# oledboard.net
KiCad netlist of a schematic drawn in EAGLE
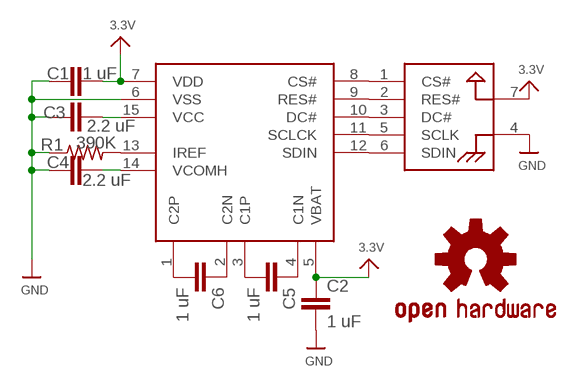
[diagram p0: schematic, sheet 1]

(export (version "E")
  (design (tool "Eeschema 10.0.6"))
  (components
    (comp (ref "C1")
      (value "1 uF")
      (footprint "eagle-import:C0805")
      (libsource (lib "eagle-import") (part "C-EUC0805"))
    )
    (comp (ref "C2")
      (value "1 uF")
      (footprint "eagle-import:C0805")
      (libsource (lib "eagle-import") (part "C-EUC0805"))
    )
    (comp (ref "C3")
      (value "2.2 uF")
      (footprint "eagle-import:C0805")
      (libsource (lib "eagle-import") (part "C-EUC0805"))
    )
    (comp (ref "C4")
      (value "2.2 uF")
      (footprint "eagle-import:C0805")
      (libsource (lib "eagle-import") (part "C-EUC0805"))
    )
    (comp (ref "C5")
      (value "1 uF")
      (footprint "eagle-import:C0805")
      (libsource (lib "eagle-import") (part "C-EUC0805"))
    )
    (comp (ref "C6")
      (value "1 uF")
      (footprint "eagle-import:C0805")
      (libsource (lib "eagle-import") (part "C-EUC0805"))
    )
    (comp (ref "LOGO1")
      (value "OSHW.SYMS")
      (footprint "eagle-import:OSHW-LOGO-S")
      (libsource (lib "eagle-import") (part "OSHW.SYMS"))
    )
    (comp (ref "R1")
      (value "390K")
      (footprint "eagle-import:R0805")
      (libsource (lib "eagle-import") (part "R-US_R0805"))
    )
    (comp (ref "U$1")
      (value "UG-2832HSWEG04")
      (footprint "eagle-import:UG-2832HSWEG04")
      (libsource (lib "eagle-import") (part "UG-2832HSWEG04"))
    )
    (comp (ref "U$6")
      (value "CONNECTOR")
      (footprint "eagle-import:CONNECTOR")
      (libsource (lib "eagle-import") (part "CONNECTOR"))
    )
  )
  (nets
    (net (code "1") (name "3.3V") (class "Default")
      (node (ref "C1") (pin "2") (pinfunction "2_2") (pintype "passive"))
      (node (ref "C2") (pin "1") (pinfunction "1_1") (pintype "passive"))
      (node (ref "U$1") (pin "5") (pinfunction "VBAT_5") (pintype "bidirectional"))
      (node (ref "U$1") (pin "7") (pinfunction "VDD_7") (pintype "bidirectional"))
      (node (ref "U$6") (pin "7") (pinfunction "GND_7") (pintype "bidirectional"))
    )
    (net (code "2") (name "GND") (class "Default")
      (node (ref "C1") (pin "1") (pinfunction "1_1") (pintype "passive"))
      (node (ref "C2") (pin "2") (pinfunction "2_2") (pintype "passive"))
      (node (ref "C3") (pin "1") (pinfunction "1_1") (pintype "passive"))
      (node (ref "C4") (pin "1") (pinfunction "1_1") (pintype "passive"))
      (node (ref "R1") (pin "1") (pinfunction "1_1") (pintype "passive"))
      (node (ref "U$1") (pin "6") (pinfunction "VSS_6") (pintype "bidirectional"))
      (node (ref "U$6") (pin "4") (pinfunction "3.3V_4") (pintype "bidirectional"))
    )
    (net (code "3") (name "Net-(U$1-C1N)") (class "Default")
      (node (ref "C5") (pin "1") (pinfunction "1_1") (pintype "passive"))
      (node (ref "U$1") (pin "4") (pinfunction "C1N_4") (pintype "bidirectional"))
    )
    (net (code "4") (name "Net-(U$1-C1P)") (class "Default")
      (node (ref "C5") (pin "2") (pinfunction "2_2") (pintype "passive"))
      (node (ref "U$1") (pin "3") (pinfunction "C1P_3") (pintype "bidirectional"))
    )
    (net (code "5") (name "Net-(U$1-C2N)") (class "Default")
      (node (ref "C6") (pin "1") (pinfunction "1_1") (pintype "passive"))
      (node (ref "U$1") (pin "2") (pinfunction "C2N_2") (pintype "bidirectional"))
    )
    (net (code "6") (name "Net-(U$1-C2P)") (class "Default")
      (node (ref "C6") (pin "2") (pinfunction "2_2") (pintype "passive"))
      (node (ref "U$1") (pin "1") (pinfunction "C2P_1") (pintype "bidirectional"))
    )
    (net (code "7") (name "Net-(U$1-CS#)") (class "Default")
      (node (ref "U$1") (pin "8") (pinfunction "CS#_8") (pintype "bidirectional"))
      (node (ref "U$6") (pin "1") (pinfunction "CS#_1") (pintype "bidirectional"))
    )
    (net (code "8") (name "Net-(U$1-DC#)") (class "Default")
      (node (ref "U$1") (pin "10") (pinfunction "DC#_10") (pintype "bidirectional"))
      (node (ref "U$6") (pin "3") (pinfunction "DC#_3") (pintype "bidirectional"))
    )
    (net (code "9") (name "Net-(U$1-IREF)") (class "Default")
      (node (ref "R1") (pin "2") (pinfunction "2_2") (pintype "passive"))
      (node (ref "U$1") (pin "13") (pinfunction "IREF_13") (pintype "bidirectional"))
    )
    (net (code "10") (name "Net-(U$1-RES#)") (class "Default")
      (node (ref "U$1") (pin "9") (pinfunction "RES#_9") (pintype "bidirectional"))
      (node (ref "U$6") (pin "2") (pinfunction "RES#_2") (pintype "bidirectional"))
    )
    (net (code "11") (name "Net-(U$1-SCLCK)") (class "Default")
      (node (ref "U$1") (pin "11") (pinfunction "SCLCK_11") (pintype "bidirectional"))
      (node (ref "U$6") (pin "5") (pinfunction "SCLK_5") (pintype "bidirectional"))
    )
    (net (code "12") (name "Net-(U$1-SDIN)") (class "Default")
      (node (ref "U$1") (pin "12") (pinfunction "SDIN_12") (pintype "bidirectional"))
      (node (ref "U$6") (pin "6") (pinfunction "SDIN_6") (pintype "bidirectional"))
    )
    (net (code "13") (name "Net-(U$1-VCC)") (class "Default")
      (node (ref "C3") (pin "2") (pinfunction "2_2") (pintype "passive"))
      (node (ref "U$1") (pin "15") (pinfunction "VCC_15") (pintype "bidirectional"))
    )
    (net (code "14") (name "Net-(U$1-VCOMH)") (class "Default")
      (node (ref "C4") (pin "2") (pinfunction "2_2") (pintype "passive"))
      (node (ref "U$1") (pin "14") (pinfunction "VCOMH_14") (pintype "bidirectional"))
    )
  )
)
